# Power_supply.net
KiCad netlist of a schematic drawn in Altium Designer
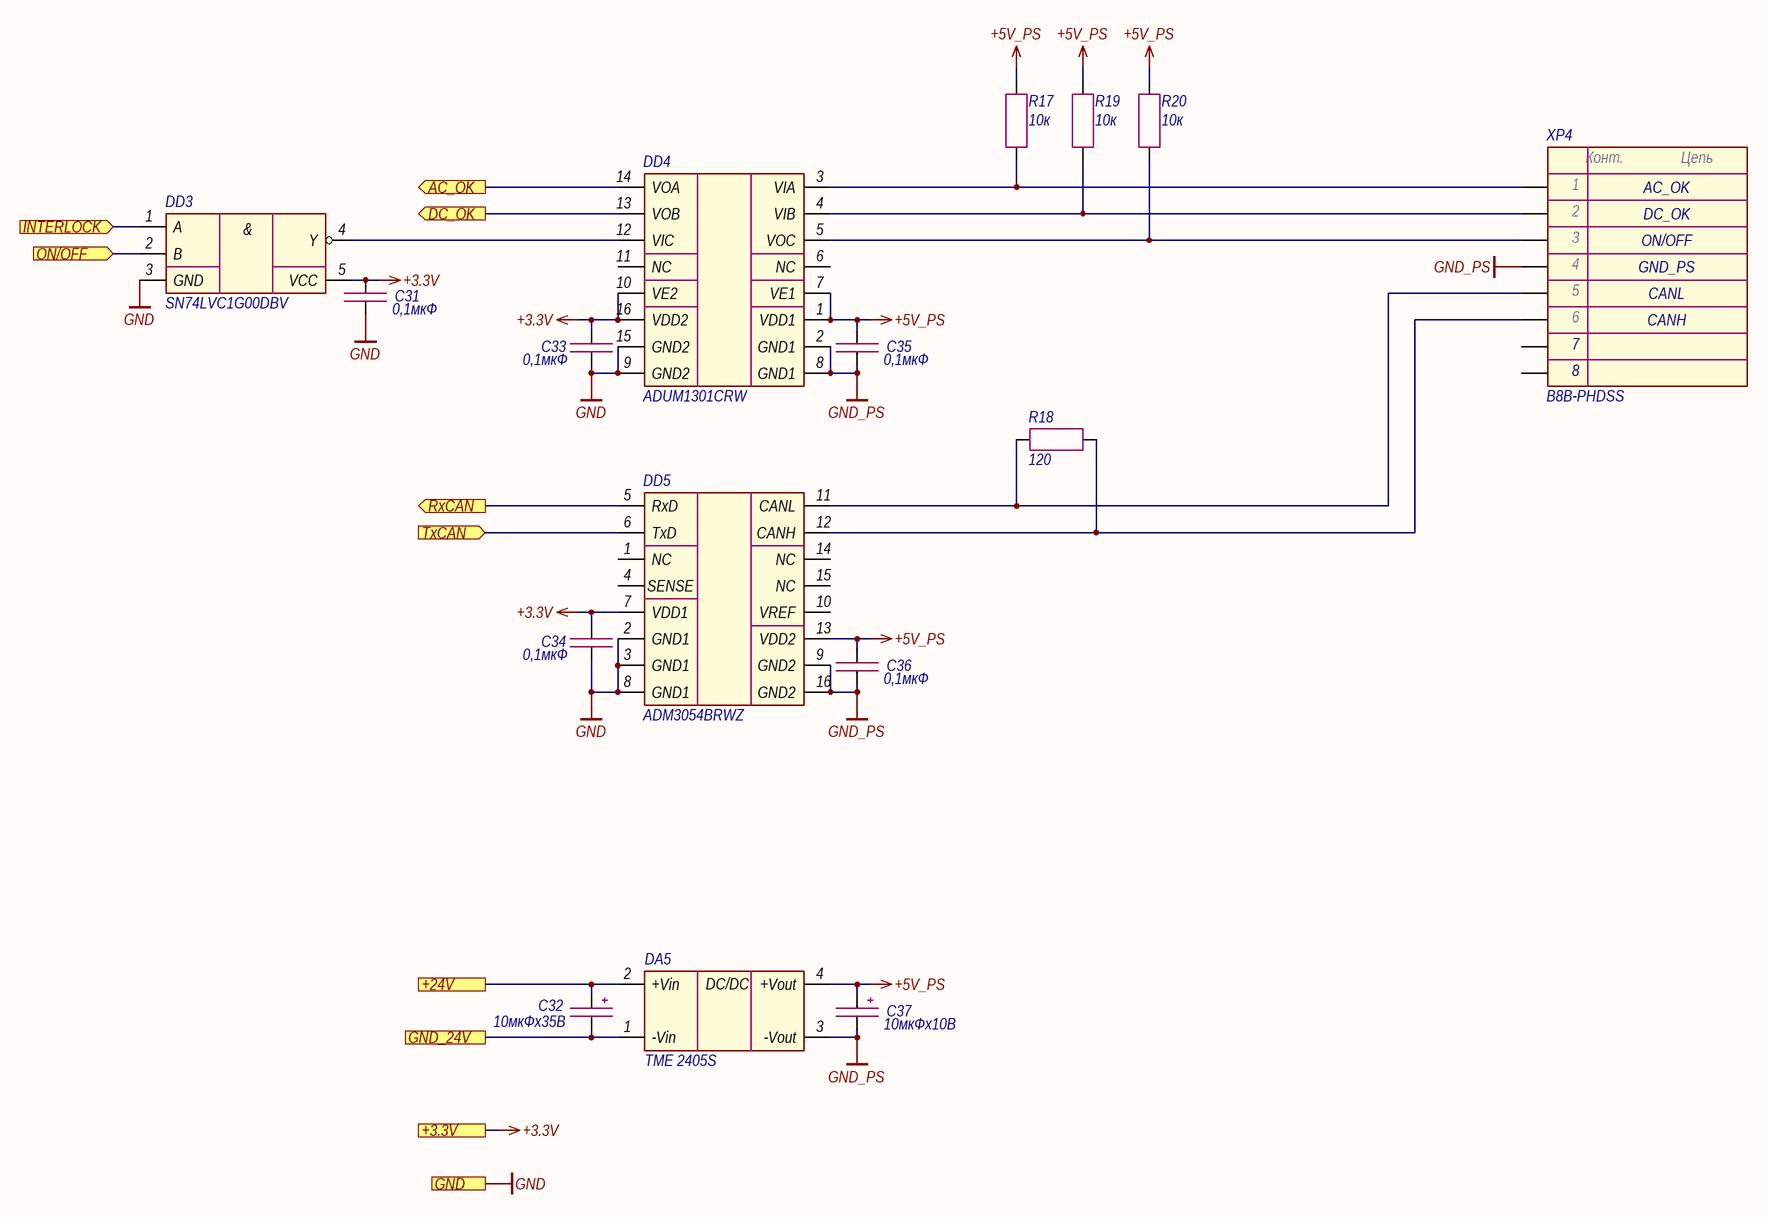
[diagram p0: Power_supply.SchDoc]

(export (version "E")
  (design (tool "Eeschema 10.0.6"))
  (components
    (comp (ref "C31")
      (value "0,1мкФ")
      (footprint "Pcb_library:CAP_0603")
      (fields (field (name "MANUFACTURER") "Murata"))
      (libsource (lib "Schem_library") (part "Capacitor"))
    )
    (comp (ref "C32")
      (value "10мкФх35B")
      (footprint "Pcb_library:CAP_C")
      (libsource (lib "Schem_library") (part "Capacitor_Polar"))
    )
    (comp (ref "C33")
      (value "0,1мкФ")
      (footprint "Pcb_library:CAP_0603")
      (fields (field (name "MANUFACTURER") "Murata"))
      (libsource (lib "Schem_library") (part "Capacitor"))
    )
    (comp (ref "C34")
      (value "0,1мкФ")
      (footprint "Pcb_library:CAP_0603")
      (fields (field (name "MANUFACTURER") "Murata"))
      (libsource (lib "Schem_library") (part "Capacitor"))
    )
    (comp (ref "C35")
      (value "0,1мкФ")
      (footprint "Pcb_library:CAP_0603")
      (fields (field (name "MANUFACTURER") "Murata"))
      (libsource (lib "Schem_library") (part "Capacitor"))
    )
    (comp (ref "C36")
      (value "0,1мкФ")
      (footprint "Pcb_library:CAP_0603")
      (fields (field (name "MANUFACTURER") "Murata"))
      (libsource (lib "Schem_library") (part "Capacitor"))
    )
    (comp (ref "C37")
      (value "10мкФх10B")
      (footprint "Pcb_library:CAP_A")
      (libsource (lib "Schem_library") (part "Capacitor_Polar"))
    )
    (comp (ref "DA5")
      (value "TME 2405S")
      (footprint "Pcb_library:TME (SIP-4)")
      (fields (field (name "MANUFACTURER") "Traco Power"))
      (libsource (lib "Schem_library") (part "TME"))
    )
    (comp (ref "DD3")
      (value "SN74LVC1G00DBV")
      (footprint "Pcb_library:SOT-23-5")
      (fields (field (name "MANUFACTURER") "Texas Instruments"))
      (libsource (lib "Schem_library") (part "SN74LVC1G00"))
    )
    (comp (ref "DD4")
      (value "ADUM1301CRW")
      (footprint "Pcb_library:SOIC-16W")
      (fields (field (name "MANUFACTURER") "Analog Devices"))
      (libsource (lib "Schem_library") (part "ADUM1301"))
    )
    (comp (ref "DD5")
      (value "ADM3054BRWZ")
      (footprint "Pcb_library:SOIC-16W")
      (fields (field (name "MANUFACTURER") "Analog Devices"))
      (libsource (lib "Schem_library") (part "ADM3054BRWZ"))
    )
    (comp (ref "R17")
      (value "10к")
      (footprint "Pcb_library:RES_0603")
      (fields (field (name "MANUFACTURER") "Yageo"))
      (libsource (lib "Schem_library") (part "Resistor"))
    )
    (comp (ref "R18")
      (value "120")
      (footprint "Pcb_library:RES_0805")
      (fields (field (name "MANUFACTURER") "Yageo"))
      (libsource (lib "Schem_library") (part "Resistor"))
    )
    (comp (ref "R19")
      (value "10к")
      (footprint "Pcb_library:RES_0603")
      (fields (field (name "MANUFACTURER") "Yageo"))
      (libsource (lib "Schem_library") (part "Resistor"))
    )
    (comp (ref "R20")
      (value "10к")
      (footprint "Pcb_library:RES_0603")
      (fields (field (name "MANUFACTURER") "Yageo"))
      (libsource (lib "Schem_library") (part "Resistor"))
    )
    (comp (ref "XP4")
      (value "B8B-PHDSS")
      (footprint "Pcb_library:B8B-PHDSS")
      (fields (field (name "MANUFACTURER") "JST"))
      (libsource (lib "Schem_library") (part "Connector-8"))
    )
  )
  (nets
    (net (code "1") (name "+3.3V") (class "Default")
      (node (ref "C31") (pin "1") (pinfunction "1_1") (pintype "passive"))
      (node (ref "C33") (pin "1") (pinfunction "1_1") (pintype "passive"))
      (node (ref "C34") (pin "1") (pinfunction "1_1") (pintype "passive"))
      (node (ref "DD3") (pin "5") (pinfunction "VCC_5") (pintype "passive"))
      (node (ref "DD4") (pin "10") (pinfunction "VE2_10") (pintype "passive"))
      (node (ref "DD4") (pin "16") (pinfunction "VDD2_16") (pintype "passive"))
      (node (ref "DD5") (pin "7") (pinfunction "VDD1_7") (pintype "passive"))
    )
    (net (code "2") (name "+5V_PS") (class "Default")
      (node (ref "C35") (pin "1") (pinfunction "1_1") (pintype "passive"))
      (node (ref "C36") (pin "1") (pinfunction "1_1") (pintype "passive"))
      (node (ref "C37") (pin "1") (pinfunction "1_1") (pintype "passive"))
      (node (ref "DA5") (pin "4") (pinfunction "+Vout_4") (pintype "passive"))
      (node (ref "DD4") (pin "1") (pinfunction "VDD1_1") (pintype "passive"))
      (node (ref "DD4") (pin "7") (pinfunction "VE1_7") (pintype "passive"))
      (node (ref "DD5") (pin "13") (pinfunction "VDD2_13") (pintype "passive"))
      (node (ref "R17") (pin "1") (pinfunction "1_1") (pintype "passive"))
      (node (ref "R19") (pin "1") (pinfunction "1_1") (pintype "passive"))
      (node (ref "R20") (pin "1") (pinfunction "1_1") (pintype "passive"))
    )
    (net (code "3") (name "/+24V") (class "Default")
      (node (ref "C32") (pin "1") (pinfunction "1_1") (pintype "passive"))
      (node (ref "DA5") (pin "2") (pinfunction "+Vin_2") (pintype "passive"))
    )
    (net (code "4") (name "/AC_OK") (class "Default")
      (node (ref "DD4") (pin "14") (pinfunction "VOA_14") (pintype "passive"))
    )
    (net (code "5") (name "/DC_OK") (class "Default")
      (node (ref "DD4") (pin "13") (pinfunction "VOB_13") (pintype "passive"))
    )
    (net (code "6") (name "/GND_24V") (class "Default")
      (node (ref "C32") (pin "2") (pinfunction "2_2") (pintype "passive"))
      (node (ref "DA5") (pin "1") (pinfunction "-Vin_1") (pintype "passive"))
    )
    (net (code "7") (name "/INTERLOCK") (class "Default")
      (node (ref "DD3") (pin "1") (pinfunction "A_1") (pintype "passive"))
    )
    (net (code "8") (name "/ON{slash}OFF") (class "Default")
      (node (ref "DD3") (pin "2") (pinfunction "B_2") (pintype "passive"))
    )
    (net (code "9") (name "/RxCAN") (class "Default")
      (node (ref "DD5") (pin "5") (pinfunction "RxD_5") (pintype "passive"))
    )
    (net (code "10") (name "/TxCAN") (class "Default")
      (node (ref "DD5") (pin "6") (pinfunction "TxD_6") (pintype "passive"))
    )
    (net (code "11") (name "GND") (class "Default")
      (node (ref "C31") (pin "2") (pinfunction "2_2") (pintype "passive"))
      (node (ref "C33") (pin "2") (pinfunction "2_2") (pintype "passive"))
      (node (ref "C34") (pin "2") (pinfunction "2_2") (pintype "passive"))
      (node (ref "DD3") (pin "3") (pinfunction "GND_3") (pintype "passive"))
      (node (ref "DD4") (pin "15") (pinfunction "GND2_15") (pintype "passive"))
      (node (ref "DD4") (pin "9") (pinfunction "GND2_9") (pintype "passive"))
      (node (ref "DD5") (pin "2") (pinfunction "GND1_2") (pintype "passive"))
      (node (ref "DD5") (pin "3") (pinfunction "GND1_3") (pintype "passive"))
      (node (ref "DD5") (pin "8") (pinfunction "GND1_8") (pintype "passive"))
    )
    (net (code "12") (name "GND_PS") (class "Default")
      (node (ref "C35") (pin "2") (pinfunction "2_2") (pintype "passive"))
      (node (ref "C36") (pin "2") (pinfunction "2_2") (pintype "passive"))
      (node (ref "C37") (pin "2") (pinfunction "2_2") (pintype "passive"))
      (node (ref "DA5") (pin "3") (pinfunction "-Vout_3") (pintype "passive"))
      (node (ref "DD4") (pin "2") (pinfunction "GND1_2") (pintype "passive"))
      (node (ref "DD4") (pin "8") (pinfunction "GND1_8") (pintype "passive"))
      (node (ref "DD5") (pin "16") (pinfunction "GND2_16") (pintype "passive"))
      (node (ref "DD5") (pin "9") (pinfunction "GND2_9") (pintype "passive"))
      (node (ref "XP4") (pin "4") (pintype "passive"))
    )
    (net (code "13") (name "Net-(DD3-Y)") (class "Default")
      (node (ref "DD3") (pin "4") (pinfunction "Y_4") (pintype "passive"))
      (node (ref "DD4") (pin "12") (pinfunction "VIC_12") (pintype "passive"))
    )
    (net (code "14") (name "Net-(DD4-VIA)") (class "Default")
      (node (ref "DD4") (pin "3") (pinfunction "VIA_3") (pintype "passive"))
      (node (ref "R17") (pin "2") (pinfunction "2_2") (pintype "passive"))
      (node (ref "XP4") (pin "1") (pintype "passive"))
    )
    (net (code "15") (name "Net-(DD4-VIB)") (class "Default")
      (node (ref "DD4") (pin "4") (pinfunction "VIB_4") (pintype "passive"))
      (node (ref "R19") (pin "2") (pinfunction "2_2") (pintype "passive"))
      (node (ref "XP4") (pin "2") (pintype "passive"))
    )
    (net (code "16") (name "Net-(DD4-VOC)") (class "Default")
      (node (ref "DD4") (pin "5") (pinfunction "VOC_5") (pintype "passive"))
      (node (ref "R20") (pin "2") (pinfunction "2_2") (pintype "passive"))
      (node (ref "XP4") (pin "3") (pintype "passive"))
    )
    (net (code "17") (name "Net-(DD5-CANH)") (class "Default")
      (node (ref "DD5") (pin "12") (pinfunction "CANH_12") (pintype "passive"))
      (node (ref "R18") (pin "2") (pinfunction "2_2") (pintype "passive"))
      (node (ref "XP4") (pin "6") (pintype "passive"))
    )
    (net (code "18") (name "Net-(DD5-CANL)") (class "Default")
      (node (ref "DD5") (pin "11") (pinfunction "CANL_11") (pintype "passive"))
      (node (ref "R18") (pin "1") (pinfunction "1_1") (pintype "passive"))
      (node (ref "XP4") (pin "5") (pintype "passive"))
    )
    (net (code "19") (name "unconnected-(DD4-NC-Pad6)") (class "Default")
      (node (ref "DD4") (pin "6") (pinfunction "NC_6") (pintype "passive"))
    )
    (net (code "20") (name "unconnected-(DD4-NC-Pad11)") (class "Default")
      (node (ref "DD4") (pin "11") (pinfunction "NC_11") (pintype "passive"))
    )
    (net (code "21") (name "unconnected-(DD5-NC-Pad1)") (class "Default")
      (node (ref "DD5") (pin "1") (pinfunction "NC_1") (pintype "passive"))
    )
    (net (code "22") (name "unconnected-(DD5-NC-Pad14)") (class "Default")
      (node (ref "DD5") (pin "14") (pinfunction "NC_14") (pintype "passive"))
    )
    (net (code "23") (name "unconnected-(DD5-NC-Pad15)") (class "Default")
      (node (ref "DD5") (pin "15") (pinfunction "NC_15") (pintype "passive"))
    )
    (net (code "24") (name "unconnected-(DD5-SENSE-Pad4)") (class "Default")
      (node (ref "DD5") (pin "4") (pinfunction "SENSE_4") (pintype "passive"))
    )
    (net (code "25") (name "unconnected-(DD5-VREF-Pad10)") (class "Default")
      (node (ref "DD5") (pin "10") (pinfunction "VREF_10") (pintype "passive"))
    )
    (net (code "26") (name "unconnected-(XP4-Pad7)") (class "Default")
      (node (ref "XP4") (pin "7") (pintype "passive"))
    )
    (net (code "27") (name "unconnected-(XP4-Pad8)") (class "Default")
      (node (ref "XP4") (pin "8") (pintype "passive"))
    )
  )
)
